# LCD.net
KiCad netlist of a schematic drawn in Altium Designer
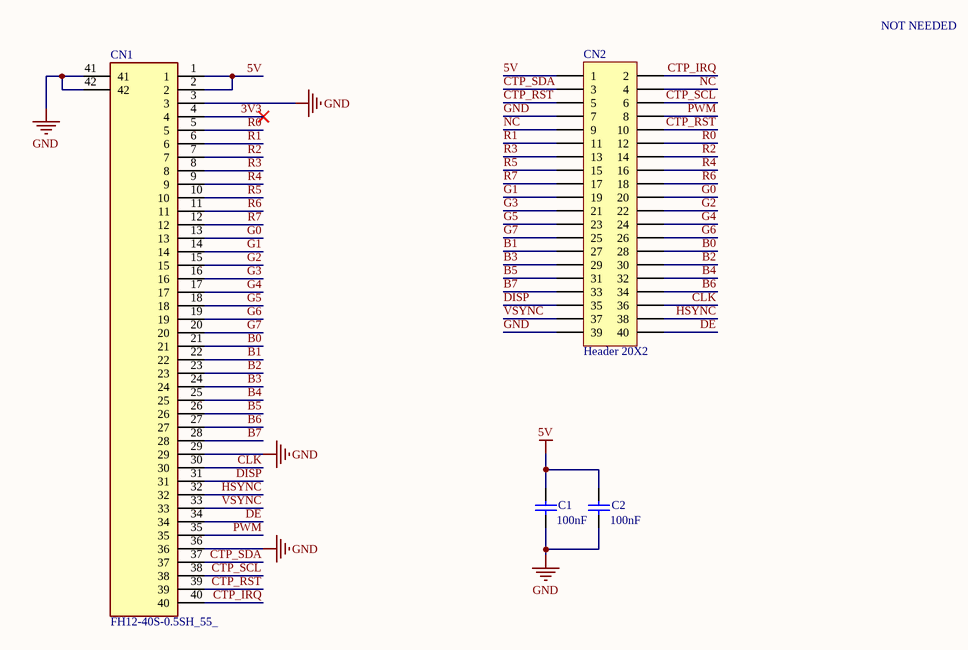
[diagram p0: LCD.SchDoc]

(export (version "E")
  (design (tool "Eeschema 10.0.6"))
  (components
    (comp (ref "C1")
      (value "100nF")
      (footprint "RAD-0.3")
      (description "Capacitor")
      (fields (field (name "Comment") "X5R") (field (name "PUBLISHER") "Altium Limited"))
      (libsource (lib "Miscellaneous Devices") (part "Cap"))
    )
    (comp (ref "C2")
      (value "100nF")
      (footprint "RAD-0.3")
      (description "Capacitor")
      (fields (field (name "Comment") "X5R") (field (name "PUBLISHER") "Altium Limited"))
      (libsource (lib "Miscellaneous Devices") (part "Cap"))
    )
    (comp (ref "CN1")
      (value "FH12-40S-0.5SH_55_")
      (footprint "SamacSys:FH1240S05SH55")
      (description "Connector")
      (fields
        (field (name "MANUFACTURER_PART_NUMBER") "FH12-40S-0.5SH(55)")
        (field (name "MOUSER PART NUMBER") "798-FH12-40S-0.5SH55")
      )
      (libsource (lib "*") (part "FH12-40S-0.5SH_55_"))
    )
    (comp (ref "CN2")
      (value "Header 20X2")
      (footprint "HDR2X20")
      (description "Header, 20-Pin, Dual row")
      (fields (field (name "PUBLISHER") "Altium Limited"))
      (libsource (lib "Miscellaneous Connectors") (part "Header 20X2"))
    )
  )
  (nets
    (net (code "1") (name "/3V3") (class "Default")
      (node (ref "CN1") (pin "4") (pinfunction "4_4") (pintype "passive+no_connect"))
    )
    (net (code "2") (name "/B0") (class "Default")
      (node (ref "CN1") (pin "21") (pinfunction "21_21") (pintype "passive"))
      (node (ref "CN2") (pin "28") (pinfunction "28_28") (pintype "passive"))
    )
    (net (code "3") (name "/B1") (class "Default")
      (node (ref "CN1") (pin "22") (pinfunction "22_22") (pintype "passive"))
      (node (ref "CN2") (pin "27") (pinfunction "27_27") (pintype "passive"))
    )
    (net (code "4") (name "/B2") (class "Default")
      (node (ref "CN1") (pin "23") (pinfunction "23_23") (pintype "passive"))
      (node (ref "CN2") (pin "30") (pinfunction "30_30") (pintype "passive"))
    )
    (net (code "5") (name "/B3") (class "Default")
      (node (ref "CN1") (pin "24") (pinfunction "24_24") (pintype "passive"))
      (node (ref "CN2") (pin "29") (pinfunction "29_29") (pintype "passive"))
    )
    (net (code "6") (name "/B4") (class "Default")
      (node (ref "CN1") (pin "25") (pinfunction "25_25") (pintype "passive"))
      (node (ref "CN2") (pin "32") (pinfunction "32_32") (pintype "passive"))
    )
    (net (code "7") (name "/B5") (class "Default")
      (node (ref "CN1") (pin "26") (pinfunction "26_26") (pintype "passive"))
      (node (ref "CN2") (pin "31") (pinfunction "31_31") (pintype "passive"))
    )
    (net (code "8") (name "/B6") (class "Default")
      (node (ref "CN1") (pin "27") (pinfunction "27_27") (pintype "passive"))
      (node (ref "CN2") (pin "34") (pinfunction "34_34") (pintype "passive"))
    )
    (net (code "9") (name "/B7") (class "Default")
      (node (ref "CN1") (pin "28") (pinfunction "28_28") (pintype "passive"))
      (node (ref "CN2") (pin "33") (pinfunction "33_33") (pintype "passive"))
    )
    (net (code "10") (name "/CLK") (class "Default")
      (node (ref "CN1") (pin "30") (pinfunction "30_30") (pintype "passive"))
      (node (ref "CN2") (pin "36") (pinfunction "36_36") (pintype "passive"))
    )
    (net (code "11") (name "/CTP_IRQ") (class "Default")
      (node (ref "CN1") (pin "40") (pinfunction "40_40") (pintype "passive"))
      (node (ref "CN2") (pin "2") (pinfunction "2_2") (pintype "passive"))
    )
    (net (code "12") (name "/CTP_RST") (class "Default")
      (node (ref "CN1") (pin "39") (pinfunction "39_39") (pintype "passive"))
      (node (ref "CN2") (pin "10") (pinfunction "10_10") (pintype "passive"))
      (node (ref "CN2") (pin "5") (pinfunction "5_5") (pintype "passive"))
    )
    (net (code "13") (name "/CTP_SCL") (class "Default")
      (node (ref "CN1") (pin "38") (pinfunction "38_38") (pintype "passive"))
      (node (ref "CN2") (pin "6") (pinfunction "6_6") (pintype "passive"))
    )
    (net (code "14") (name "/CTP_SDA") (class "Default")
      (node (ref "CN1") (pin "37") (pinfunction "37_37") (pintype "passive"))
      (node (ref "CN2") (pin "3") (pinfunction "3_3") (pintype "passive"))
    )
    (net (code "15") (name "/DE") (class "Default")
      (node (ref "CN1") (pin "34") (pinfunction "34_34") (pintype "passive"))
      (node (ref "CN2") (pin "40") (pinfunction "40_40") (pintype "passive"))
    )
    (net (code "16") (name "/DISP") (class "Default")
      (node (ref "CN1") (pin "31") (pinfunction "31_31") (pintype "passive"))
      (node (ref "CN2") (pin "35") (pinfunction "35_35") (pintype "passive"))
    )
    (net (code "17") (name "/G0") (class "Default")
      (node (ref "CN1") (pin "13") (pinfunction "13_13") (pintype "passive"))
      (node (ref "CN2") (pin "20") (pinfunction "20_20") (pintype "passive"))
    )
    (net (code "18") (name "/G1") (class "Default")
      (node (ref "CN1") (pin "14") (pinfunction "14_14") (pintype "passive"))
      (node (ref "CN2") (pin "19") (pinfunction "19_19") (pintype "passive"))
    )
    (net (code "19") (name "/G2") (class "Default")
      (node (ref "CN1") (pin "15") (pinfunction "15_15") (pintype "passive"))
      (node (ref "CN2") (pin "22") (pinfunction "22_22") (pintype "passive"))
    )
    (net (code "20") (name "/G3") (class "Default")
      (node (ref "CN1") (pin "16") (pinfunction "16_16") (pintype "passive"))
      (node (ref "CN2") (pin "21") (pinfunction "21_21") (pintype "passive"))
    )
    (net (code "21") (name "/G4") (class "Default")
      (node (ref "CN1") (pin "17") (pinfunction "17_17") (pintype "passive"))
      (node (ref "CN2") (pin "24") (pinfunction "24_24") (pintype "passive"))
    )
    (net (code "22") (name "/G5") (class "Default")
      (node (ref "CN1") (pin "18") (pinfunction "18_18") (pintype "passive"))
      (node (ref "CN2") (pin "23") (pinfunction "23_23") (pintype "passive"))
    )
    (net (code "23") (name "/G6") (class "Default")
      (node (ref "CN1") (pin "19") (pinfunction "19_19") (pintype "passive"))
      (node (ref "CN2") (pin "26") (pinfunction "26_26") (pintype "passive"))
    )
    (net (code "24") (name "/G7") (class "Default")
      (node (ref "CN1") (pin "20") (pinfunction "20_20") (pintype "passive"))
      (node (ref "CN2") (pin "25") (pinfunction "25_25") (pintype "passive"))
    )
    (net (code "25") (name "/HSYNC") (class "Default")
      (node (ref "CN1") (pin "32") (pinfunction "32_32") (pintype "passive"))
      (node (ref "CN2") (pin "38") (pinfunction "38_38") (pintype "passive"))
    )
    (net (code "26") (name "/NC") (class "Default")
      (node (ref "CN2") (pin "4") (pinfunction "4_4") (pintype "passive"))
      (node (ref "CN2") (pin "9") (pinfunction "9_9") (pintype "passive"))
    )
    (net (code "27") (name "/PWM") (class "Default")
      (node (ref "CN1") (pin "35") (pinfunction "35_35") (pintype "passive"))
      (node (ref "CN2") (pin "8") (pinfunction "8_8") (pintype "passive"))
    )
    (net (code "28") (name "/R0") (class "Default")
      (node (ref "CN1") (pin "5") (pinfunction "5_5") (pintype "passive"))
      (node (ref "CN2") (pin "12") (pinfunction "12_12") (pintype "passive"))
    )
    (net (code "29") (name "/R1") (class "Default")
      (node (ref "CN1") (pin "6") (pinfunction "6_6") (pintype "passive"))
      (node (ref "CN2") (pin "11") (pinfunction "11_11") (pintype "passive"))
    )
    (net (code "30") (name "/R2") (class "Default")
      (node (ref "CN1") (pin "7") (pinfunction "7_7") (pintype "passive"))
      (node (ref "CN2") (pin "14") (pinfunction "14_14") (pintype "passive"))
    )
    (net (code "31") (name "/R3") (class "Default")
      (node (ref "CN1") (pin "8") (pinfunction "8_8") (pintype "passive"))
      (node (ref "CN2") (pin "13") (pinfunction "13_13") (pintype "passive"))
    )
    (net (code "32") (name "/R4") (class "Default")
      (node (ref "CN1") (pin "9") (pinfunction "9_9") (pintype "passive"))
      (node (ref "CN2") (pin "16") (pinfunction "16_16") (pintype "passive"))
    )
    (net (code "33") (name "/R5") (class "Default")
      (node (ref "CN1") (pin "10") (pinfunction "10_10") (pintype "passive"))
      (node (ref "CN2") (pin "15") (pinfunction "15_15") (pintype "passive"))
    )
    (net (code "34") (name "/R6") (class "Default")
      (node (ref "CN1") (pin "11") (pinfunction "11_11") (pintype "passive"))
      (node (ref "CN2") (pin "18") (pinfunction "18_18") (pintype "passive"))
    )
    (net (code "35") (name "/R7") (class "Default")
      (node (ref "CN1") (pin "12") (pinfunction "12_12") (pintype "passive"))
      (node (ref "CN2") (pin "17") (pinfunction "17_17") (pintype "passive"))
    )
    (net (code "36") (name "/VSYNC") (class "Default")
      (node (ref "CN1") (pin "33") (pinfunction "33_33") (pintype "passive"))
      (node (ref "CN2") (pin "37") (pinfunction "37_37") (pintype "passive"))
    )
    (net (code "37") (name "5V") (class "Default")
      (node (ref "C1") (pin "1") (pinfunction "1_1") (pintype "passive"))
      (node (ref "C2") (pin "1") (pinfunction "1_1") (pintype "passive"))
      (node (ref "CN1") (pin "1") (pinfunction "1_1") (pintype "passive"))
      (node (ref "CN1") (pin "2") (pinfunction "2_2") (pintype "passive"))
      (node (ref "CN2") (pin "1") (pinfunction "1_1") (pintype "passive"))
    )
    (net (code "38") (name "GND") (class "Default")
      (node (ref "C1") (pin "2") (pinfunction "2_2") (pintype "passive"))
      (node (ref "C2") (pin "2") (pinfunction "2_2") (pintype "passive"))
      (node (ref "CN1") (pin "29") (pinfunction "29_29") (pintype "passive"))
      (node (ref "CN1") (pin "3") (pinfunction "3_3") (pintype "passive"))
      (node (ref "CN1") (pin "36") (pinfunction "36_36") (pintype "passive"))
      (node (ref "CN1") (pin "41") (pinfunction "41_41") (pintype "passive"))
      (node (ref "CN1") (pin "42") (pinfunction "42_42") (pintype "passive"))
      (node (ref "CN2") (pin "39") (pinfunction "39_39") (pintype "passive"))
      (node (ref "CN2") (pin "7") (pinfunction "7_7") (pintype "passive"))
    )
  )
)
